# control_board.net
KiCad netlist of a schematic drawn in EAGLE
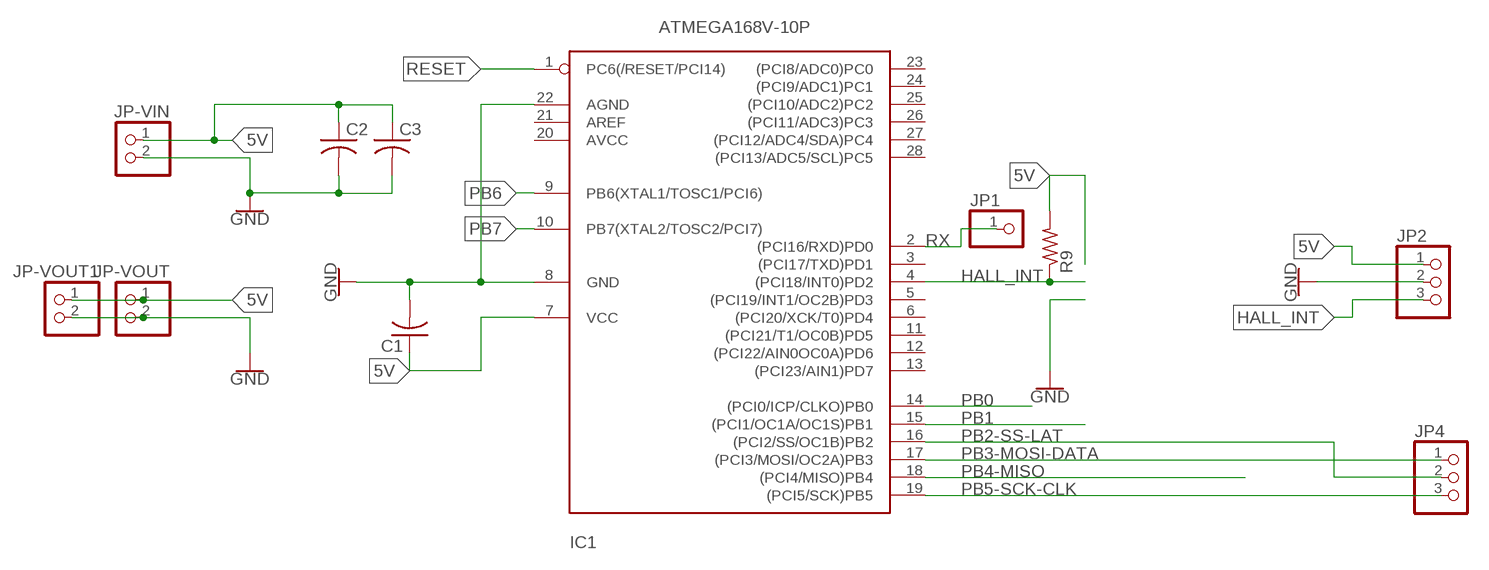
[diagram p0: schematic, sheet 1]

(export (version "E")
  (design (tool "Eeschema 10.0.6"))
  (components
    (comp (ref "C1")
      (value "C-US025-030X050")
      (footprint "eagle-import:C025-030X050")
      (libsource (lib "eagle-import") (part "C-US025-030X050"))
    )
    (comp (ref "C2")
      (value "C-US025-060X050")
      (footprint "eagle-import:C025-060X050")
      (libsource (lib "eagle-import") (part "C-US025-060X050"))
    )
    (comp (ref "C3")
      (value "C-US025-060X050")
      (footprint "eagle-import:C025-060X050")
      (libsource (lib "eagle-import") (part "C-US025-060X050"))
    )
    (comp (ref "IC1")
      (value "ATMEGA168V-10P")
      (footprint "eagle-import:DIL28-3")
      (libsource (lib "eagle-import") (part "ATMEGA168PV-10"))
    )
    (comp (ref "JP-VIN")
      (value "PINHD-1X2")
      (footprint "eagle-import:1X02")
      (libsource (lib "eagle-import") (part "PINHD-1X2"))
    )
    (comp (ref "JP-VOUT")
      (value "PINHD-1X2")
      (footprint "eagle-import:1X02")
      (libsource (lib "eagle-import") (part "PINHD-1X2"))
    )
    (comp (ref "JP-VOUT1")
      (value "PINHD-1X2")
      (footprint "eagle-import:1X02")
      (libsource (lib "eagle-import") (part "PINHD-1X2"))
    )
    (comp (ref "JP1")
      (value "PINHD-1X1")
      (footprint "eagle-import:1X01")
      (libsource (lib "eagle-import") (part "PINHD-1X1"))
    )
    (comp (ref "JP2")
      (value "PINHD-1X3")
      (footprint "eagle-import:1X03")
      (libsource (lib "eagle-import") (part "PINHD-1X3"))
    )
    (comp (ref "JP4")
      (value "PINHD-1X3")
      (footprint "eagle-import:1X03")
      (libsource (lib "eagle-import") (part "PINHD-1X3"))
    )
    (comp (ref "R9")
      (value "R-US_0207/7")
      (footprint "eagle-import:0207_7")
      (libsource (lib "eagle-import") (part "R-US_0207/7"))
    )
  )
  (nets
    (net (code "1") (name "/PB0") (class "Default")
      (node (ref "IC1") (pin "14") (pinfunction "(PCI0/ICP/CLKO)PB0_14") (pintype "bidirectional"))
    )
    (net (code "2") (name "/PB1") (class "Default")
      (node (ref "IC1") (pin "15") (pinfunction "(PCI1/OC1A/OC1S)PB1_15") (pintype "bidirectional"))
    )
    (net (code "3") (name "/PB2-SS-LAT") (class "Default")
      (node (ref "IC1") (pin "16") (pinfunction "(PCI2/SS/OC1B)PB2_16") (pintype "bidirectional"))
      (node (ref "JP4") (pin "2") (pinfunction "2_2") (pintype "passive"))
    )
    (net (code "4") (name "/PB3-MOSI-DATA") (class "Default")
      (node (ref "IC1") (pin "17") (pinfunction "(PCI3/MOSI/OC2A)PB3_17") (pintype "bidirectional"))
      (node (ref "JP4") (pin "1") (pinfunction "1_1") (pintype "passive"))
    )
    (net (code "5") (name "/PB4-MISO") (class "Default")
      (node (ref "IC1") (pin "18") (pinfunction "(PCI4/MISO)PB4_18") (pintype "bidirectional"))
    )
    (net (code "6") (name "/PB5-SCK-CLK") (class "Default")
      (node (ref "IC1") (pin "19") (pinfunction "(PCI5/SCK)PB5_19") (pintype "bidirectional"))
      (node (ref "JP4") (pin "3") (pinfunction "3_3") (pintype "passive"))
    )
    (net (code "7") (name "/RX") (class "Default")
      (node (ref "IC1") (pin "2") (pinfunction "(PCI16/RXD)PD0_2") (pintype "bidirectional"))
      (node (ref "JP1") (pin "1") (pinfunction "1_1") (pintype "passive"))
    )
    (net (code "8") (name "5V") (class "Default")
      (node (ref "C1") (pin "1") (pinfunction "1_1") (pintype "passive"))
      (node (ref "C2") (pin "1") (pinfunction "1_1") (pintype "passive"))
      (node (ref "C3") (pin "1") (pinfunction "1_1") (pintype "passive"))
      (node (ref "IC1") (pin "7") (pinfunction "VCC_7") (pintype "bidirectional"))
      (node (ref "JP-VIN") (pin "1") (pinfunction "1_1") (pintype "passive"))
      (node (ref "JP-VOUT") (pin "1") (pinfunction "1_1") (pintype "passive"))
      (node (ref "JP-VOUT1") (pin "1") (pinfunction "1_1") (pintype "passive"))
      (node (ref "JP2") (pin "1") (pinfunction "1_1") (pintype "passive"))
      (node (ref "R9") (pin "2") (pinfunction "2_2") (pintype "passive"))
    )
    (net (code "9") (name "GND") (class "Default")
      (node (ref "C1") (pin "2") (pinfunction "2_2") (pintype "passive"))
      (node (ref "C2") (pin "2") (pinfunction "2_2") (pintype "passive"))
      (node (ref "C3") (pin "2") (pinfunction "2_2") (pintype "passive"))
      (node (ref "IC1") (pin "22") (pinfunction "AGND_22") (pintype "bidirectional"))
      (node (ref "IC1") (pin "8") (pinfunction "GND_8") (pintype "bidirectional"))
      (node (ref "JP-VIN") (pin "2") (pinfunction "2_2") (pintype "passive"))
      (node (ref "JP-VOUT") (pin "2") (pinfunction "2_2") (pintype "passive"))
      (node (ref "JP-VOUT1") (pin "2") (pinfunction "2_2") (pintype "passive"))
      (node (ref "JP2") (pin "2") (pinfunction "2_2") (pintype "passive"))
    )
    (net (code "10") (name "HALL_INT") (class "Default")
      (node (ref "IC1") (pin "4") (pinfunction "(PCI18/INT0)PD2_4") (pintype "bidirectional"))
      (node (ref "JP2") (pin "3") (pinfunction "3_3") (pintype "passive"))
      (node (ref "R9") (pin "1") (pinfunction "1_1") (pintype "passive"))
    )
    (net (code "11") (name "PB6") (class "Default")
      (node (ref "IC1") (pin "9") (pinfunction "PB6(XTAL1/TOSC1/PCI6)_9") (pintype "bidirectional"))
    )
    (net (code "12") (name "PB7") (class "Default")
      (node (ref "IC1") (pin "10") (pinfunction "PB7(XTAL2/TOSC2/PCI7)_10") (pintype "bidirectional"))
    )
    (net (code "13") (name "RESET") (class "Default")
      (node (ref "IC1") (pin "1") (pinfunction "PC6(/RESET/PCI14)_1") (pintype "bidirectional"))
    )
    (net (code "14") (name "unconnected-(IC1-(PCI8{slash}ADC0)PC0-Pad23)") (class "Default")
      (node (ref "IC1") (pin "23") (pinfunction "(PCI8/ADC0)PC0_23") (pintype "bidirectional"))
    )
    (net (code "15") (name "unconnected-(IC1-(PCI9{slash}ADC1)PC1-Pad24)") (class "Default")
      (node (ref "IC1") (pin "24") (pinfunction "(PCI9/ADC1)PC1_24") (pintype "bidirectional"))
    )
    (net (code "16") (name "unconnected-(IC1-(PCI10{slash}ADC2)PC2-Pad25)") (class "Default")
      (node (ref "IC1") (pin "25") (pinfunction "(PCI10/ADC2)PC2_25") (pintype "bidirectional"))
    )
    (net (code "17") (name "unconnected-(IC1-(PCI11{slash}ADC3)PC3-Pad26)") (class "Default")
      (node (ref "IC1") (pin "26") (pinfunction "(PCI11/ADC3)PC3_26") (pintype "bidirectional"))
    )
    (net (code "18") (name "unconnected-(IC1-(PCI12{slash}ADC4{slash}SDA)PC4-Pad27)") (class "Default")
      (node (ref "IC1") (pin "27") (pinfunction "(PCI12/ADC4/SDA)PC4_27") (pintype "bidirectional"))
    )
    (net (code "19") (name "unconnected-(IC1-(PCI13{slash}ADC5{slash}SCL)PC5-Pad28)") (class "Default")
      (node (ref "IC1") (pin "28") (pinfunction "(PCI13/ADC5/SCL)PC5_28") (pintype "bidirectional"))
    )
    (net (code "20") (name "unconnected-(IC1-(PCI17{slash}TXD)PD1-Pad3)") (class "Default")
      (node (ref "IC1") (pin "3") (pinfunction "(PCI17/TXD)PD1_3") (pintype "bidirectional"))
    )
    (net (code "21") (name "unconnected-(IC1-(PCI19{slash}INT1{slash}OC2B)PD3-Pad5)") (class "Default")
      (node (ref "IC1") (pin "5") (pinfunction "(PCI19/INT1/OC2B)PD3_5") (pintype "bidirectional"))
    )
    (net (code "22") (name "unconnected-(IC1-(PCI20{slash}XCK{slash}T0)PD4-Pad6)") (class "Default")
      (node (ref "IC1") (pin "6") (pinfunction "(PCI20/XCK/T0)PD4_6") (pintype "bidirectional"))
    )
    (net (code "23") (name "unconnected-(IC1-(PCI21{slash}T1{slash}OC0B)PD5-Pad11)") (class "Default")
      (node (ref "IC1") (pin "11") (pinfunction "(PCI21/T1/OC0B)PD5_11") (pintype "bidirectional"))
    )
    (net (code "24") (name "unconnected-(IC1-(PCI22{slash}AIN0OC0A)PD6-Pad12)") (class "Default")
      (node (ref "IC1") (pin "12") (pinfunction "(PCI22/AIN0OC0A)PD6_12") (pintype "bidirectional"))
    )
    (net (code "25") (name "unconnected-(IC1-(PCI23{slash}AIN1)PD7-Pad13)") (class "Default")
      (node (ref "IC1") (pin "13") (pinfunction "(PCI23/AIN1)PD7_13") (pintype "bidirectional"))
    )
    (net (code "26") (name "unconnected-(IC1-AREF-Pad21)") (class "Default")
      (node (ref "IC1") (pin "21") (pinfunction "AREF_21") (pintype "bidirectional"))
    )
    (net (code "27") (name "unconnected-(IC1-AVCC-Pad20)") (class "Default")
      (node (ref "IC1") (pin "20") (pinfunction "AVCC_20") (pintype "bidirectional"))
    )
  )
)
